# ZynqPeripherals.net
KiCad netlist of a schematic drawn in Altium Designer
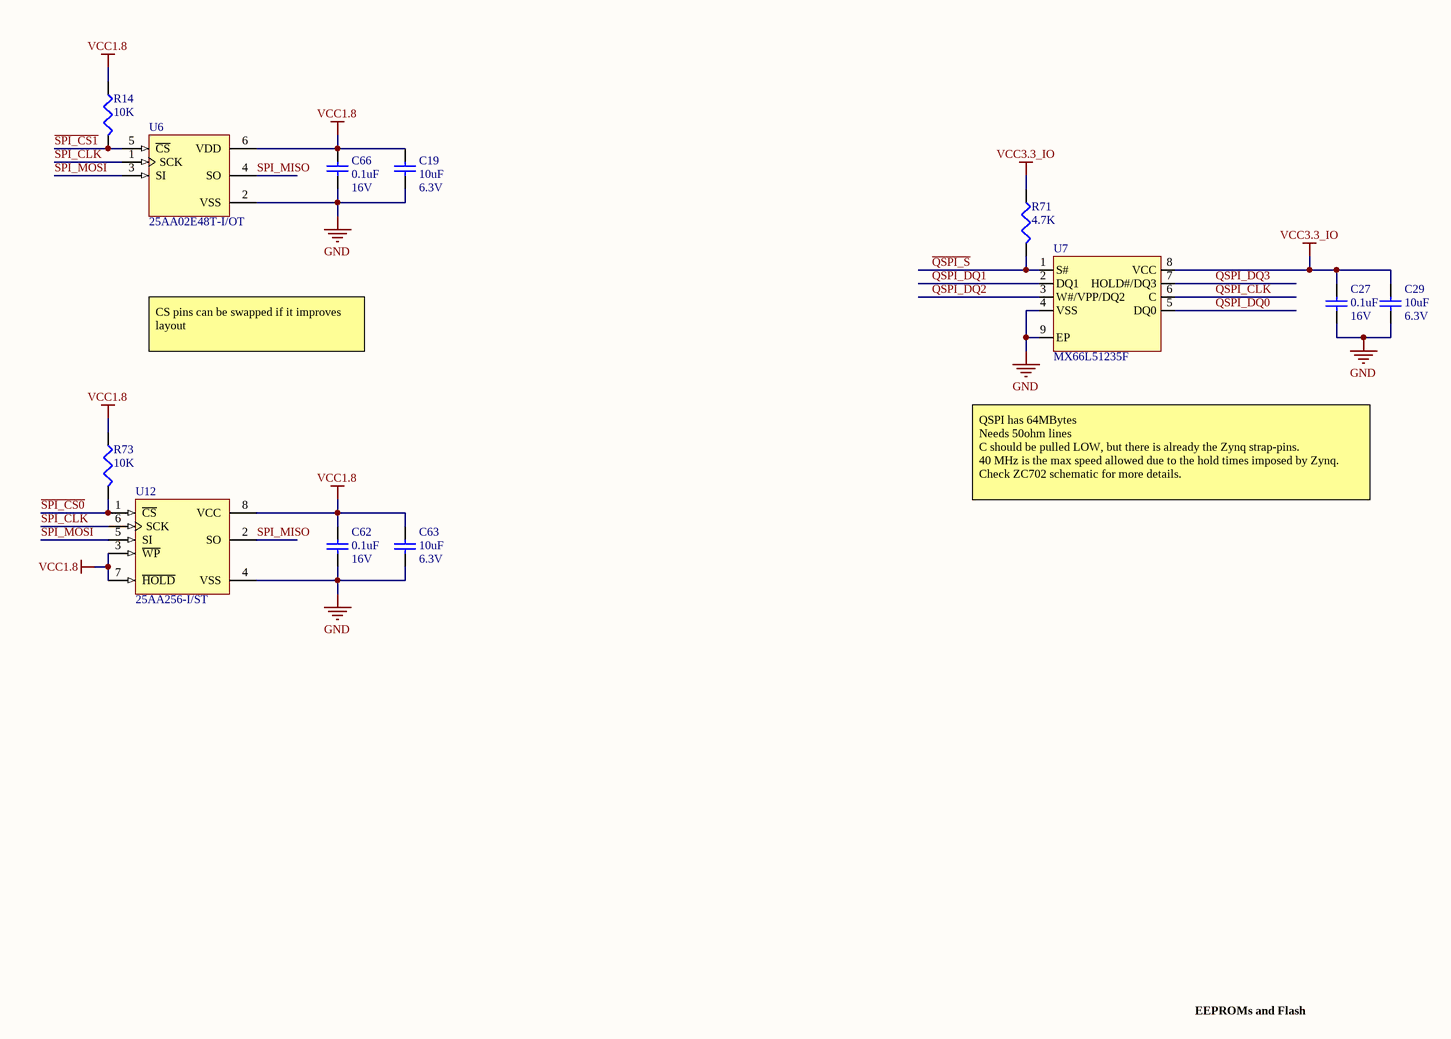
[diagram p0: ZynqPeripherals.SchDoc]

(export (version "E")
  (design (tool "Eeschema 10.0.6"))
  (components
    (comp (ref "C19")
      (value "10uF")
      (footprint "C0402_IPC_H")
      (description "Capacitor")
      (fields
        (field (name "RATING") "6.3V")
        (field (name "MANUFACTURER") "Murata")
        (field (name "PART") "GRM155R60J106ME44D")
      )
      (libsource (lib "CustomParts") (part "Cap"))
    )
    (comp (ref "C27")
      (value "0.1uF")
      (footprint "C0402_IPC_H")
      (description "Capacitor")
      (fields
        (field (name "RATING") "16V")
        (field (name "MANUFACTURER") "Murata")
        (field (name "PART") "GRM155R71C104KA88D")
      )
      (libsource (lib "CustomParts") (part "Cap"))
    )
    (comp (ref "C29")
      (value "10uF")
      (footprint "C0402_IPC_H")
      (description "Capacitor")
      (fields
        (field (name "RATING") "6.3V")
        (field (name "MANUFACTURER") "Murata")
        (field (name "PART") "GRM155R60J106ME44D")
      )
      (libsource (lib "CustomParts") (part "Cap"))
    )
    (comp (ref "C62")
      (value "0.1uF")
      (footprint "C0402_IPC_H")
      (description "Capacitor")
      (fields
        (field (name "RATING") "16V")
        (field (name "MANUFACTURER") "Murata")
        (field (name "PART") "GRM155R71C104KA88D")
      )
      (libsource (lib "CustomParts") (part "Cap"))
    )
    (comp (ref "C63")
      (value "10uF")
      (footprint "C0402_IPC_H")
      (description "Capacitor")
      (fields
        (field (name "RATING") "6.3V")
        (field (name "MANUFACTURER") "Murata")
        (field (name "PART") "GRM155R60J106ME44D")
      )
      (libsource (lib "CustomParts") (part "Cap"))
    )
    (comp (ref "C66")
      (value "0.1uF")
      (footprint "C0402_IPC_H")
      (description "Capacitor")
      (fields
        (field (name "RATING") "16V")
        (field (name "MANUFACTURER") "Murata")
        (field (name "PART") "GRM155R71C104KA88D")
      )
      (libsource (lib "CustomParts") (part "Cap"))
    )
    (comp (ref "R14")
      (value "10K")
      (footprint "R0201_IPC_H")
      (description "Resistor")
      (fields (field (name "TOLERANCE") "1%") (field (name "MANUFACTURER") "Panasonic"))
      (libsource (lib "CustomParts") (part "Res"))
    )
    (comp (ref "R71")
      (value "4.7K")
      (footprint "R0402_IPC_H")
      (description "Resistor")
      (fields (field (name "TOLERANCE") "1%") (field (name "MANUFACTURER") "Panasonic"))
      (libsource (lib "CustomParts") (part "Res"))
    )
    (comp (ref "R73")
      (value "10K")
      (footprint "R0201_IPC_H")
      (description "Resistor")
      (fields (field (name "TOLERANCE") "1%") (field (name "MANUFACTURER") "Panasonic"))
      (libsource (lib "CustomParts") (part "Res"))
    )
    (comp (ref "U6")
      (value "25AA02E48T-I/OT")
      (footprint "SOT-23-OT6_L")
      (fields (field (name "MANUFACTURER") "Microchip"))
      (libsource (lib "altium-import") (part "root_0_CMP-0165-00270-1_"))
    )
    (comp (ref "U7")
      (value "MX66L51235F")
      (footprint "SON127P800X80_HS-9_N")
      (description "3V, 512M-bit [x1/x2/x4], CMOS MXSMIO (serial multi I/O) Flash Memory")
      (fields (field (name "PART") "MX66L51235FZ2I-10G") (field (name "MANUFACTURER") "Macronix"))
      (libsource (lib "CustomParts") (part "MX66L51235F"))
    )
    (comp (ref "U12")
      (value "25AA256-I/ST")
      (footprint "TSSOP-ST8_L")
      (description "256K SPI Bus Serial EEPROM, 8-Pin TSSOP, Industrial Temperature")
      (fields (field (name "MANUFACTURER") "Microchip"))
      (libsource (lib "altium-import") (part "root_0_CMP-0165-00405-1_"))
    )
  )
  (nets
    (net (code "1") (name "/QSPI_CLK") (class "Default")
      (node (ref "U7") (pin "6") (pinfunction "C_6") (pintype "passive"))
    )
    (net (code "2") (name "/QSPI_DQ0") (class "Default")
      (node (ref "U7") (pin "5") (pinfunction "DQ0_5") (pintype "passive"))
    )
    (net (code "3") (name "/QSPI_DQ1") (class "Default")
      (node (ref "U7") (pin "2") (pinfunction "DQ1_2") (pintype "passive"))
    )
    (net (code "4") (name "/QSPI_DQ2") (class "Default")
      (node (ref "U7") (pin "3") (pinfunction "W#/VPP/DQ2_3") (pintype "passive"))
    )
    (net (code "5") (name "/QSPI_DQ3") (class "Default")
      (node (ref "U7") (pin "7") (pinfunction "HOLD#/DQ3_7") (pintype "passive"))
    )
    (net (code "6") (name "/QSPI_S") (class "Default")
      (node (ref "R71") (pin "2") (pinfunction "2_2") (pintype "passive"))
      (node (ref "U7") (pin "1") (pinfunction "S#_1") (pintype "passive"))
    )
    (net (code "7") (name "/SPI_CLK") (class "Default")
      (node (ref "U12") (pin "6") (pinfunction "SCK_6") (pintype "input"))
      (node (ref "U6") (pin "1") (pinfunction "SCK_1") (pintype "input"))
    )
    (net (code "8") (name "/SPI_CS0") (class "Default")
      (node (ref "R73") (pin "2") (pinfunction "2_2") (pintype "passive"))
      (node (ref "U12") (pin "1") (pinfunction "~{CS}_1") (pintype "input"))
    )
    (net (code "9") (name "/SPI_CS1") (class "Default")
      (node (ref "R14") (pin "2") (pinfunction "2_2") (pintype "passive"))
      (node (ref "U6") (pin "5") (pinfunction "~{CS}_5") (pintype "input"))
    )
    (net (code "10") (name "/SPI_MISO") (class "Default")
      (node (ref "U12") (pin "2") (pinfunction "SO_2") (pintype "tri_state"))
      (node (ref "U6") (pin "4") (pinfunction "SO_4") (pintype "tri_state"))
    )
    (net (code "11") (name "/SPI_MOSI") (class "Default")
      (node (ref "U12") (pin "5") (pinfunction "SI_5") (pintype "input"))
      (node (ref "U6") (pin "3") (pinfunction "SI_3") (pintype "input"))
    )
    (net (code "12") (name "GND") (class "Default")
      (node (ref "C19") (pin "2") (pinfunction "2_2") (pintype "passive"))
      (node (ref "C27") (pin "2") (pinfunction "2_2") (pintype "passive"))
      (node (ref "C29") (pin "2") (pinfunction "2_2") (pintype "passive"))
      (node (ref "C62") (pin "2") (pinfunction "2_2") (pintype "passive"))
      (node (ref "C63") (pin "2") (pinfunction "2_2") (pintype "passive"))
      (node (ref "C66") (pin "2") (pinfunction "2_2") (pintype "passive"))
      (node (ref "U12") (pin "4") (pinfunction "VSS_4") (pintype "power_in"))
      (node (ref "U6") (pin "2") (pinfunction "VSS_2") (pintype "power_in"))
      (node (ref "U7") (pin "4") (pinfunction "VSS_4") (pintype "passive"))
      (node (ref "U7") (pin "9") (pinfunction "EP_9") (pintype "passive"))
    )
    (net (code "13") (name "VCC1.8") (class "Default")
      (node (ref "C19") (pin "1") (pinfunction "1_1") (pintype "passive"))
      (node (ref "C62") (pin "1") (pinfunction "1_1") (pintype "passive"))
      (node (ref "C63") (pin "1") (pinfunction "1_1") (pintype "passive"))
      (node (ref "C66") (pin "1") (pinfunction "1_1") (pintype "passive"))
      (node (ref "R14") (pin "1") (pinfunction "1_1") (pintype "passive"))
      (node (ref "R73") (pin "1") (pinfunction "1_1") (pintype "passive"))
      (node (ref "U12") (pin "3") (pinfunction "~{WP}_3") (pintype "input"))
      (node (ref "U12") (pin "7") (pinfunction "~{HOLD}_7") (pintype "input"))
      (node (ref "U12") (pin "8") (pinfunction "VCC_8") (pintype "power_in"))
      (node (ref "U6") (pin "6") (pinfunction "VDD_6") (pintype "power_in"))
    )
    (net (code "14") (name "VCC3.3_IO") (class "Default")
      (node (ref "C27") (pin "1") (pinfunction "1_1") (pintype "passive"))
      (node (ref "C29") (pin "1") (pinfunction "1_1") (pintype "passive"))
      (node (ref "R71") (pin "1") (pinfunction "1_1") (pintype "passive"))
      (node (ref "U7") (pin "8") (pinfunction "VCC_8") (pintype "passive"))
    )
  )
)
